# Driver.net
KiCad netlist of a schematic drawn in Altium Designer
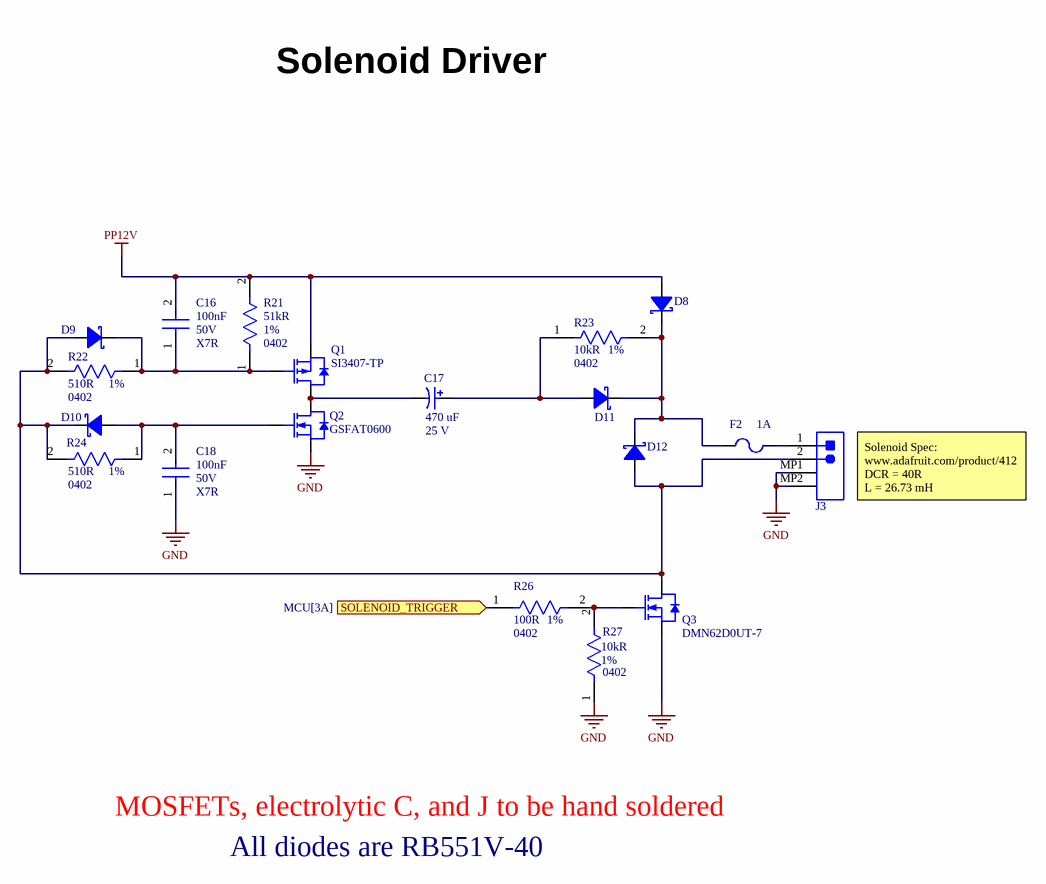
[diagram p0: Driver.SchDoc]

(export (version "E")
  (design (tool "Eeschema 10.0.6"))
  (components
    (comp (ref "C16")
      (value "CL05B104KB54PNC")
      (footprint "CAP0402")
      (description "50V 100nF X7R ±10% 0402  Multilayer Ceramic Capacitors MLCC - SMD/SMT ROHS")
      (fields
        (field (name "TOLERANCE") "±20%")
        (field (name "MANUFACTURER") "Samsung Electro-Mechanics")
        (field (name "DIELECTRIC") "X7R")
        (field (name "VOLTAGE RATING") "50V")
        (field (name "CAPACITANCE") "100nF")
      )
      (libsource (lib "FYDP_library_sch") (part "CAP0402"))
    )
    (comp (ref "C17")
      (value "UUD1E471MNL1GS")
      (footprint "NIC-CAPA2-10X10_V")
      (fields
        (field (name "RATED CAPACITANCE") "470 uF")
        (field (name "MANUFACTURER") "Nichicon")
        (field (name "RATED VOLTAGE") "25 V")
      )
      (libsource (lib "Altium Content Vault") (part "NIC-CAP-P-2"))
    )
    (comp (ref "C18")
      (value "CL05B104KB54PNC")
      (footprint "CAP0402")
      (description "50V 100nF X7R ±10% 0402  Multilayer Ceramic Capacitors MLCC - SMD/SMT ROHS")
      (fields
        (field (name "TOLERANCE") "±20%")
        (field (name "MANUFACTURER") "Samsung Electro-Mechanics")
        (field (name "DIELECTRIC") "X7R")
        (field (name "VOLTAGE RATING") "50V")
        (field (name "CAPACITANCE") "100nF")
      )
      (libsource (lib "FYDP_library_sch") (part "CAP0402"))
    )
    (comp (ref "D8")
      (value "RB551V-40")
      (footprint "SOD-323")
      (description "40V 470mV@500mA 0.5A SOD-323  Schottky Barrier Diodes (SBD) ROHS")
      (fields (field (name "MANUFACTURER") "Taiwan Semiconductor"))
      (libsource (lib "FYDP_library_sch") (part "RB551V-40"))
    )
    (comp (ref "D9")
      (value "RB551V-40")
      (footprint "SOD-323")
      (description "40V 470mV@500mA 0.5A SOD-323  Schottky Barrier Diodes (SBD) ROHS")
      (fields (field (name "MANUFACTURER") "Taiwan Semiconductor"))
      (libsource (lib "FYDP_library_sch") (part "RB551V-40"))
    )
    (comp (ref "D10")
      (value "RB551V-40")
      (footprint "SOD-323")
      (description "40V 470mV@500mA 0.5A SOD-323  Schottky Barrier Diodes (SBD) ROHS")
      (fields (field (name "MANUFACTURER") "Taiwan Semiconductor"))
      (libsource (lib "FYDP_library_sch") (part "RB551V-40"))
    )
    (comp (ref "D11")
      (value "RB551V-40")
      (footprint "SOD-323")
      (description "40V 470mV@500mA 0.5A SOD-323  Schottky Barrier Diodes (SBD) ROHS")
      (fields (field (name "MANUFACTURER") "Taiwan Semiconductor"))
      (libsource (lib "FYDP_library_sch") (part "RB551V-40"))
    )
    (comp (ref "D12")
      (value "RB551V-40")
      (footprint "SOD-323")
      (description "40V 470mV@500mA 0.5A SOD-323  Schottky Barrier Diodes (SBD) ROHS")
      (fields (field (name "MANUFACTURER") "Taiwan Semiconductor"))
      (libsource (lib "FYDP_library_sch") (part "RB551V-40"))
    )
    (comp (ref "F2")
      (value "0467001.NRHF")
      (footprint "FUSE_0603")
      (description "50A SMD Fuse 1A 32V 32V 0603  Fuses ROHS")
      (fields (field (name "MANUFACTURER") "Littelfuse") (field (name "CURRENT RATING") "1A"))
      (libsource (lib "FYDP_library_sch") (part "FUSE0603"))
    )
    (comp (ref "J3")
      (value "S2B-PH-SM4-TB(LF)(SN)")
      (footprint "JST- S2B-PH-SM4-TB(LF)(SN)-2_V")
      (description "Male Header, Pitch 2 mm, 1 x 2 Position, Height 5.5 mm, -25 to 85 degC, RoHS, Tape and Reel")
      (libsource (lib "Altium Content Vault") (part "CN-1P-2M-R2"))
    )
    (comp (ref "Q1")
      (value "SI3407-TP")
      (footprint "SOT23-3")
      (description "MOSFET P-CH 30V 4.1A SOT23")
      (libsource (lib "FYDP_library_sch") (part "IRLML5103TRPBF"))
    )
    (comp (ref "Q2")
      (value "GSFAT0600")
      (footprint "SOT-523")
      (description "MOSFET, N-CH, SINGLE, 0.30A, 60V")
      (libsource (lib "FYDP_library_sch") (part "DMN62D0UT-7"))
    )
    (comp (ref "Q3")
      (value "DMN62D0UT-7")
      (footprint "SOT-523")
      (description "NFET 60 V 320mA (Ta) 230mW (Ta) Surface Mount SOT-523")
      (libsource (lib "FYDP_library_sch") (part "DMN62D0UT-7"))
    )
    (comp (ref "R21")
      (value "0402WGF5102TCE")
      (footprint "RES0402")
      (description "62.5mW Thick Film Resistors ±100ppm/℃ ±1% 51kΩ 0402  Chip Resistor - Surface Mount ROHS")
      (fields
        (field (name "MANUFACTURER") "UNI-ROYAL(Uniroyal Elec)")
        (field (name "TOLERANCE") "1%")
        (field (name "RESISTANCE") "51kR")
        (field (name "PACKAGE") "0402")
      )
      (libsource (lib "FYDP_library_sch") (part "RES0402"))
    )
    (comp (ref "R22")
      (value "0402WGF5100TCE")
      (footprint "RES0402")
      (description "62.5mW Thick Film Resistors ±100ppm/℃ ±1% 510Ω 0402  Chip Resistor - Surface Mount ROHS")
      (fields
        (field (name "MANUFACTURER") "UNI-ROYAL(Uniroyal Elec)")
        (field (name "TOLERANCE") "1%")
        (field (name "RESISTANCE") "510R")
        (field (name "PACKAGE") "0402")
      )
      (libsource (lib "FYDP_library_sch") (part "RES0402"))
    )
    (comp (ref "R23")
      (value "0402WGF1002TCE")
      (footprint "RES0402")
      (description "62.5mW Thick Film Resistors ±100ppm/℃ ±1% 10kΩ 0402  Chip Resistor - Surface Mount ROHS")
      (fields
        (field (name "MANUFACTURER") "UNI-ROYAL(Uniroyal Elec)")
        (field (name "TOLERANCE") "1%")
        (field (name "RESISTANCE") "10kR")
        (field (name "PACKAGE") "0402")
      )
      (libsource (lib "FYDP_library_sch") (part "RES0402"))
    )
    (comp (ref "R24")
      (value "0402WGF5100TCE")
      (footprint "RES0402")
      (description "62.5mW Thick Film Resistors ±100ppm/℃ ±1% 510Ω 0402  Chip Resistor - Surface Mount ROHS")
      (fields
        (field (name "MANUFACTURER") "UNI-ROYAL(Uniroyal Elec)")
        (field (name "TOLERANCE") "1%")
        (field (name "RESISTANCE") "510R")
        (field (name "PACKAGE") "0402")
      )
      (libsource (lib "FYDP_library_sch") (part "RES0402"))
    )
    (comp (ref "R26")
      (value "0402WGF1000TCE")
      (footprint "RES0402")
      (description "62.5mW Thick Film Resistors ±1% ±200ppm/℃ 100Ω 0402  Chip Resistor - Surface Mount ROHS")
      (fields
        (field (name "MANUFACTURER") "UNI-ROYAL(Uniroyal Elec)")
        (field (name "TOLERANCE") "1%")
        (field (name "RESISTANCE") "100R")
        (field (name "PACKAGE") "0402")
      )
      (libsource (lib "FYDP_library_sch") (part "RES0402"))
    )
    (comp (ref "R27")
      (value "0402WGF1002TCE")
      (footprint "RES0402")
      (description "62.5mW Thick Film Resistors ±100ppm/℃ ±1% 10kΩ 0402  Chip Resistor - Surface Mount ROHS")
      (fields
        (field (name "MANUFACTURER") "UNI-ROYAL(Uniroyal Elec)")
        (field (name "TOLERANCE") "1%")
        (field (name "RESISTANCE") "10kR")
        (field (name "PACKAGE") "0402")
      )
      (libsource (lib "FYDP_library_sch") (part "RES0402"))
    )
  )
  (nets
    (net (code "1") (name "/SOLENOID_TRIGGER") (class "Default")
      (node (ref "R26") (pin "1") (pinfunction "1_1") (pintype "passive"))
    )
    (net (code "2") (name "GND") (class "Default")
      (node (ref "C18") (pin "1") (pinfunction "1_1") (pintype "passive"))
      (node (ref "J3") (pin "MP1") (pinfunction "MP1_MP1") (pintype "passive"))
      (node (ref "J3") (pin "MP2") (pinfunction "MP2_MP2") (pintype "passive"))
      (node (ref "Q2") (pin "2") (pinfunction "SOURCE_2") (pintype "passive"))
      (node (ref "Q3") (pin "2") (pinfunction "SOURCE_2") (pintype "passive"))
      (node (ref "R27") (pin "1") (pinfunction "1_1") (pintype "passive"))
    )
    (net (code "3") (name "Net-(D9-Cathode)") (class "Default")
      (node (ref "C16") (pin "1") (pinfunction "1_1") (pintype "passive"))
      (node (ref "D9") (pin "1") (pinfunction "Cathode_1") (pintype "passive"))
      (node (ref "Q1") (pin "1") (pinfunction "Gate_1") (pintype "passive"))
      (node (ref "R21") (pin "1") (pinfunction "1_1") (pintype "passive"))
      (node (ref "R22") (pin "1") (pinfunction "1_1") (pintype "passive"))
    )
    (net (code "4") (name "Net-(D10-Anode)") (class "Default")
      (node (ref "C18") (pin "2") (pinfunction "2_2") (pintype "passive"))
      (node (ref "D10") (pin "2") (pinfunction "Anode_2") (pintype "passive"))
      (node (ref "Q2") (pin "1") (pinfunction "GATE_1") (pintype "passive"))
      (node (ref "R24") (pin "1") (pinfunction "1_1") (pintype "passive"))
    )
    (net (code "5") (name "Net-(D10-Cathode)") (class "Default")
      (node (ref "D10") (pin "1") (pinfunction "Cathode_1") (pintype "passive"))
      (node (ref "D12") (pin "2") (pinfunction "Anode_2") (pintype "passive"))
      (node (ref "D9") (pin "2") (pinfunction "Anode_2") (pintype "passive"))
      (node (ref "J3") (pin "2") (pinfunction "2_2") (pintype "passive"))
      (node (ref "Q3") (pin "3") (pinfunction "DRAIN_3") (pintype "passive"))
      (node (ref "R22") (pin "2") (pinfunction "2_2") (pintype "passive"))
      (node (ref "R24") (pin "2") (pinfunction "2_2") (pintype "passive"))
    )
    (net (code "6") (name "Net-(D11-Anode)") (class "Default")
      (node (ref "C17") (pin "1") (pinfunction "1_1") (pintype "passive"))
      (node (ref "D11") (pin "2") (pinfunction "Anode_2") (pintype "passive"))
      (node (ref "R23") (pin "1") (pinfunction "1_1") (pintype "passive"))
    )
    (net (code "7") (name "Net-(D11-Cathode)") (class "Default")
      (node (ref "D11") (pin "1") (pinfunction "Cathode_1") (pintype "passive"))
      (node (ref "D12") (pin "1") (pinfunction "Cathode_1") (pintype "passive"))
      (node (ref "D8") (pin "1") (pinfunction "Cathode_1") (pintype "passive"))
      (node (ref "F2") (pin "1") (pinfunction "1_1") (pintype "passive"))
      (node (ref "R23") (pin "2") (pinfunction "2_2") (pintype "passive"))
    )
    (net (code "8") (name "Net-(F2-Pad2)") (class "Default")
      (node (ref "F2") (pin "2") (pinfunction "2_2") (pintype "passive"))
      (node (ref "J3") (pin "1") (pinfunction "1_1") (pintype "passive"))
    )
    (net (code "9") (name "Net-(Q1-Drain)") (class "Default")
      (node (ref "C17") (pin "2") (pinfunction "2_2") (pintype "passive"))
      (node (ref "Q1") (pin "3") (pinfunction "Drain_3") (pintype "passive"))
      (node (ref "Q2") (pin "3") (pinfunction "DRAIN_3") (pintype "passive"))
    )
    (net (code "10") (name "Net-(Q3-GATE)") (class "Default")
      (node (ref "Q3") (pin "1") (pinfunction "GATE_1") (pintype "passive"))
      (node (ref "R26") (pin "2") (pinfunction "2_2") (pintype "passive"))
      (node (ref "R27") (pin "2") (pinfunction "2_2") (pintype "passive"))
    )
    (net (code "11") (name "PP12V") (class "Default")
      (node (ref "C16") (pin "2") (pinfunction "2_2") (pintype "passive"))
      (node (ref "D8") (pin "2") (pinfunction "Anode_2") (pintype "passive"))
      (node (ref "Q1") (pin "2") (pinfunction "Source_2") (pintype "passive"))
      (node (ref "R21") (pin "2") (pinfunction "2_2") (pintype "passive"))
    )
  )
)
